# NE-CurrentSense-V2.net
KiCad netlist of a schematic drawn in Altium Designer
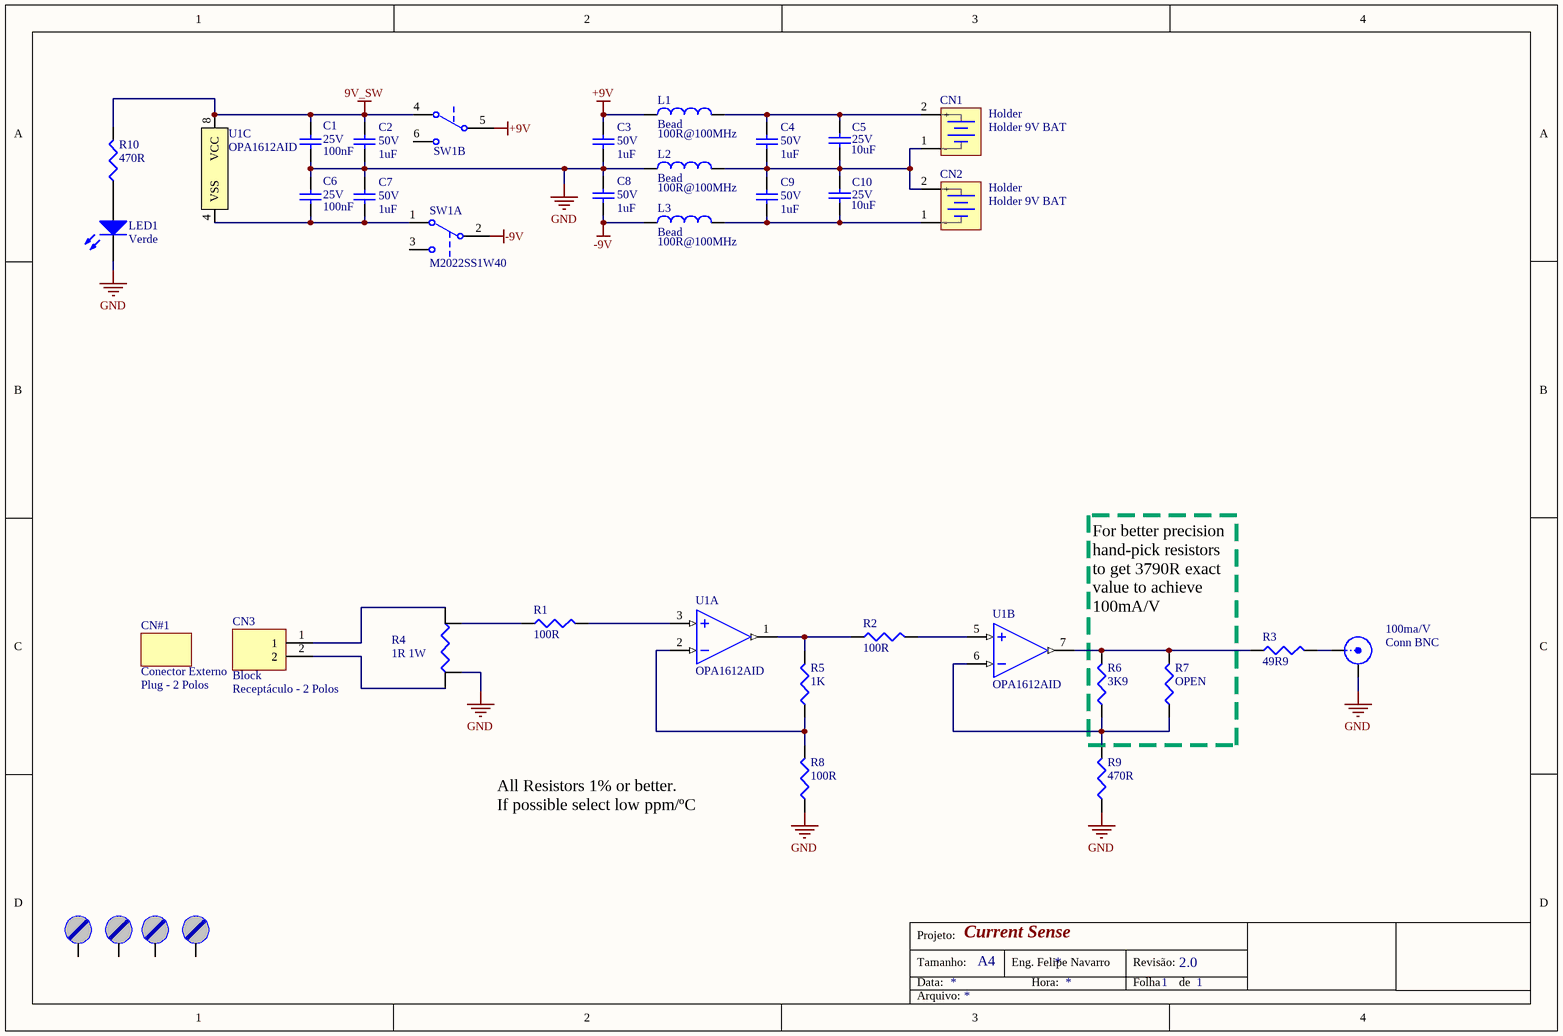
[diagram p0: NE-CurrentSense-V2.SchDoc]

(export (version "E")
  (design (tool "Eeschema 10.0.6"))
  (components
    (comp (ref "100ma/V")
      (value "Conn BNC")
      (footprint "CONN BNC-JACK")
      (description "Conector BNC")
      (libsource (lib "NavarroCON") (part "Conn BNC"))
    )
    (comp (ref "C1")
      (value "100nF")
      (footprint "CC0603")
      (description "Capacitor (Semiconductor SIM Model)")
      (fields (field (name "TENSÃO") "25V") (field (name "Comment") "Capacitor Cerâmico"))
      (libsource (lib "NavarroCAP") (part "Cap 100nF 25V 0603 X7R"))
    )
    (comp (ref "C2")
      (value "1uF")
      (footprint "CC0603")
      (description "Capacitor (Semiconductor SIM Model)")
      (fields (field (name "TENSÃO") "50V") (field (name "Comment") "Capacitor Cerâmico"))
      (libsource (lib "NavarroCAP") (part "Cap 1uF 50V 0603 X5R"))
    )
    (comp (ref "C3")
      (value "1uF")
      (footprint "CC0603")
      (description "Capacitor (Semiconductor SIM Model)")
      (fields (field (name "TENSÃO") "50V") (field (name "Comment") "Capacitor Cerâmico"))
      (libsource (lib "NavarroCAP") (part "Cap 1uF 50V 0603 X5R"))
    )
    (comp (ref "C4")
      (value "1uF")
      (footprint "CC0603")
      (description "Capacitor (Semiconductor SIM Model)")
      (fields (field (name "TENSÃO") "50V") (field (name "Comment") "Capacitor Cerâmico"))
      (libsource (lib "NavarroCAP") (part "Cap 1uF 50V 0603 X5R"))
    )
    (comp (ref "C5")
      (value "10uF")
      (footprint "CC0805")
      (description "Capacitor (Semiconductor SIM Model)")
      (fields (field (name "TENSÃO") "25V") (field (name "Comment") "Capacitor Cerâmico"))
      (libsource (lib "NavarroCAP") (part "Cap 10uF 25V 0805 X5R"))
    )
    (comp (ref "C6")
      (value "100nF")
      (footprint "CC0603")
      (description "Capacitor (Semiconductor SIM Model)")
      (fields (field (name "TENSÃO") "25V") (field (name "Comment") "Capacitor Cerâmico"))
      (libsource (lib "NavarroCAP") (part "Cap 100nF 25V 0603 X7R"))
    )
    (comp (ref "C7")
      (value "1uF")
      (footprint "CC0603")
      (description "Capacitor (Semiconductor SIM Model)")
      (fields (field (name "TENSÃO") "50V") (field (name "Comment") "Capacitor Cerâmico"))
      (libsource (lib "NavarroCAP") (part "Cap 1uF 50V 0603 X5R"))
    )
    (comp (ref "C8")
      (value "1uF")
      (footprint "CC0603")
      (description "Capacitor (Semiconductor SIM Model)")
      (fields (field (name "TENSÃO") "50V") (field (name "Comment") "Capacitor Cerâmico"))
      (libsource (lib "NavarroCAP") (part "Cap 1uF 50V 0603 X5R"))
    )
    (comp (ref "C9")
      (value "1uF")
      (footprint "CC0603")
      (description "Capacitor (Semiconductor SIM Model)")
      (fields (field (name "TENSÃO") "50V") (field (name "Comment") "Capacitor Cerâmico"))
      (libsource (lib "NavarroCAP") (part "Cap 1uF 50V 0603 X5R"))
    )
    (comp (ref "C10")
      (value "10uF")
      (footprint "CC0805")
      (description "Capacitor (Semiconductor SIM Model)")
      (fields (field (name "TENSÃO") "25V") (field (name "Comment") "Capacitor Cerâmico"))
      (libsource (lib "NavarroCAP") (part "Cap 10uF 25V 0805 X5R"))
    )
    (comp (ref "CN#1")
      (value "Conector Externo")
      (footprint "N/A")
      (description "Conector Plug")
      (fields (field (name "ALTIUM_VALUE") "Plug - 2 Polos"))
      (libsource (lib "NavarroCON") (part "Plug Block 2P 3.81mm"))
    )
    (comp (ref "CN1")
      (value "Holder")
      (footprint "BATTHOLDER-9V-BH9V-PC-ND")
      (fields (field (name "ALTIUM_VALUE") "Holder 9V BAT"))
      (libsource (lib "NavarroCON") (part "BattHolder 9V"))
    )
    (comp (ref "CN2")
      (value "Holder")
      (footprint "BATTHOLDER-9V-BH9V-PC-ND")
      (fields (field (name "ALTIUM_VALUE") "Holder 9V BAT"))
      (libsource (lib "NavarroCON") (part "BattHolder 9V"))
    )
    (comp (ref "CN3")
      (value "Block")
      (footprint "CONN BLOCK2 RCPT/H")
      (description "Conector Shrouded Block")
      (fields (field (name "ALTIUM_VALUE") "Receptáculo - 2 Polos"))
      (libsource (lib "NavarroCON") (part "SHRD Block 2P RCPT-H P3.81mm"))
    )
    (comp (ref "HOLE3")
      (value "Furo de Fixação")
      (footprint "Furo_M3")
      (description "Furo para parafuso")
      (libsource (lib "Navarro") (part "Parafuso"))
    )
    (comp (ref "HOLE4")
      (value "Furo de Fixação")
      (footprint "Furo_M3")
      (description "Furo para parafuso")
      (libsource (lib "Navarro") (part "Parafuso"))
    )
    (comp (ref "HOLE5")
      (value "Furo de Fixação")
      (footprint "Furo_M3")
      (description "Furo para parafuso")
      (libsource (lib "Navarro") (part "Parafuso"))
    )
    (comp (ref "L1")
      (value "Bead")
      (footprint "CC0603")
      (fields (field (name "ALTIUM_VALUE") "100R@100MHz"))
      (libsource (lib "NavarroIND") (part "Bd 100R@100MHz 0603 2A"))
    )
    (comp (ref "L2")
      (value "Bead")
      (footprint "CC0603")
      (fields (field (name "ALTIUM_VALUE") "100R@100MHz"))
      (libsource (lib "NavarroIND") (part "Bd 100R@100MHz 0603 2A"))
    )
    (comp (ref "L3")
      (value "Bead")
      (footprint "CC0603")
      (fields (field (name "ALTIUM_VALUE") "100R@100MHz"))
      (libsource (lib "NavarroIND") (part "Bd 100R@100MHz 0603 2A"))
    )
    (comp (ref "LED1")
      (value "Verde")
      (footprint "LED-INDIC")
      (description "Typical RED, GREEN, YELLOW, AMBER GaAs LED")
      (fields (field (name "Comment") "LED"))
      (libsource (lib "Miscellaneous Devices") (part "LED2"))
    )
    (comp (ref "R1")
      (value "100R")
      (footprint "CC0603")
      (description "Resistor")
      (libsource (lib "NavarroRES") (part "Res 100R 5% 0603 1/10W"))
    )
    (comp (ref "R2")
      (value "100R")
      (footprint "CC0603")
      (description "Resistor")
      (libsource (lib "NavarroRES") (part "Res 100R 5% 0603 1/10W"))
    )
    (comp (ref "R3")
      (value "49R9")
      (footprint "CC0603")
      (description "Resistor")
      (libsource (lib "NavarroRES") (part "Res 49R9 1% 0603 1/10W"))
    )
    (comp (ref "R4")
      (value "1R 1W")
      (footprint "CC2516 - Wide Vishay")
      (description "Resistor")
      (libsource (lib "NavarroRES") (part "Res 1R 0.1% CC2516-Wide-4W 1W"))
    )
    (comp (ref "R5")
      (value "1K")
      (footprint "CC0603")
      (description "Resistor")
      (libsource (lib "NavarroRES") (part "Res 1K 0.1% 0603 1/16W"))
    )
    (comp (ref "R6")
      (value "3K9")
      (footprint "CC0603")
      (description "Resistor")
      (libsource (lib "NavarroRES") (part "Res 3K9 1% 0603 1/10W"))
    )
    (comp (ref "R7")
      (value "OPEN")
      (footprint "CC0603")
      (description "Resistor")
      (fields (field (name "Comment") "Resistor Open"))
      (libsource (lib "NavarroRES") (part "Res Open 0603"))
    )
    (comp (ref "R8")
      (value "100R")
      (footprint "CC0603")
      (description "Resistor")
      (libsource (lib "NavarroRES") (part "Res 100R 5% 0603 1/10W"))
    )
    (comp (ref "R9")
      (value "470R")
      (footprint "CC0603")
      (description "Resistor")
      (libsource (lib "NavarroRES") (part "Res 470R 5% 0603 1/10W"))
    )
    (comp (ref "R10")
      (value "470R")
      (footprint "CC0603")
      (description "Resistor")
      (libsource (lib "NavarroRES") (part "Res 470R 5% 0603 1/10W"))
    )
    (comp (ref "SW1")
      (value "M2022SS1W40")
      (footprint "SWITCH TOGGLE DPDT 6A 125V")
      (description "Double-Pole, Double-Throw Switch")
      (libsource (lib "") (part "SW-DPDT_1"))
    )
    (comp (ref "U1")
      (value "OPA1612AID")
      (footprint "SOIC-8N")
      (description "OPAx197 36-V, Precision, Rail-to-Rail Input/Output, Low Offset Voltage, Operational Amplifiers")
      (libsource (lib "Navarro") (part "OPA2197"))
    )
  )
  (nets
    (net (code "1") (name "+9V") (class "Default")
      (node (ref "C3") (pin "2") (pinfunction "2_2") (pintype "passive"))
      (node (ref "L1") (pin "1") (pinfunction "1_1") (pintype "passive"))
      (node (ref "SW1") (pin "5") (pinfunction "C2_5") (pintype "passive"))
    )
    (net (code "2") (name "-9V") (class "Default")
      (node (ref "C8") (pin "1") (pinfunction "1_1") (pintype "passive"))
      (node (ref "L3") (pin "1") (pinfunction "1_1") (pintype "passive"))
      (node (ref "SW1") (pin "2") (pinfunction "C1_2") (pintype "passive"))
    )
    (net (code "3") (name "9V_SW") (class "Default")
      (node (ref "C1") (pin "2") (pinfunction "2_2") (pintype "passive"))
      (node (ref "C2") (pin "2") (pinfunction "2_2") (pintype "passive"))
      (node (ref "R10") (pin "2") (pinfunction "2_2") (pintype "passive"))
      (node (ref "SW1") (pin "4") (pinfunction "NC2_4") (pintype "passive"))
      (node (ref "U1") (pin "8") (pinfunction "VCC_8") (pintype "power_in"))
    )
    (net (code "4") (name "GND") (class "Default")
      (node (ref "100ma/V") (pin "2") (pinfunction "Y_2") (pintype "passive"))
      (node (ref "C1") (pin "1") (pinfunction "1_1") (pintype "passive"))
      (node (ref "C2") (pin "1") (pinfunction "1_1") (pintype "passive"))
      (node (ref "C3") (pin "1") (pinfunction "1_1") (pintype "passive"))
      (node (ref "C6") (pin "2") (pinfunction "2_2") (pintype "passive"))
      (node (ref "C7") (pin "2") (pinfunction "2_2") (pintype "passive"))
      (node (ref "C8") (pin "2") (pinfunction "2_2") (pintype "passive"))
      (node (ref "L2") (pin "1") (pinfunction "1_1") (pintype "passive"))
      (node (ref "LED1") (pin "2") (pinfunction "K_2") (pintype "passive"))
      (node (ref "R4") (pin "2") (pinfunction "2_2") (pintype "passive"))
      (node (ref "R8") (pin "1") (pinfunction "1_1") (pintype "passive"))
      (node (ref "R9") (pin "1") (pinfunction "1_1") (pintype "passive"))
    )
    (net (code "5") (name "Net-(100ma/V-X)") (class "Default")
      (node (ref "100ma/V") (pin "1") (pinfunction "X_1") (pintype "passive"))
      (node (ref "R3") (pin "2") (pinfunction "2_2") (pintype "passive"))
    )
    (net (code "6") (name "Net-(CN1-+)") (class "Default")
      (node (ref "C4") (pin "2") (pinfunction "2_2") (pintype "passive"))
      (node (ref "C5") (pin "2") (pinfunction "2_2") (pintype "passive"))
      (node (ref "CN1") (pin "2") (pinfunction "+_2") (pintype "power_in"))
      (node (ref "L1") (pin "2") (pinfunction "2_2") (pintype "passive"))
    )
    (net (code "7") (name "Net-(CN1--)") (class "Default")
      (node (ref "C10") (pin "2") (pinfunction "2_2") (pintype "passive"))
      (node (ref "C4") (pin "1") (pinfunction "1_1") (pintype "passive"))
      (node (ref "C5") (pin "1") (pinfunction "1_1") (pintype "passive"))
      (node (ref "C9") (pin "2") (pinfunction "2_2") (pintype "passive"))
      (node (ref "CN1") (pin "1") (pinfunction "-_1") (pintype "power_in"))
      (node (ref "CN2") (pin "2") (pinfunction "+_2") (pintype "power_in"))
      (node (ref "L2") (pin "2") (pinfunction "2_2") (pintype "passive"))
    )
    (net (code "8") (name "Net-(CN2--)") (class "Default")
      (node (ref "C10") (pin "1") (pinfunction "1_1") (pintype "passive"))
      (node (ref "C9") (pin "1") (pinfunction "1_1") (pintype "passive"))
      (node (ref "CN2") (pin "1") (pinfunction "-_1") (pintype "power_in"))
      (node (ref "L3") (pin "2") (pinfunction "2_2") (pintype "passive"))
    )
    (net (code "9") (name "Net-(CN3-Pad1)") (class "Default")
      (node (ref "CN3") (pin "1") (pinfunction "1_1") (pintype "passive"))
      (node (ref "R4") (pin "3") (pinfunction "3_3") (pintype "passive"))
    )
    (net (code "10") (name "Net-(CN3-Pad2)") (class "Default")
      (node (ref "CN3") (pin "2") (pinfunction "2_2") (pintype "passive"))
      (node (ref "R4") (pin "1") (pinfunction "1_1") (pintype "passive"))
    )
    (net (code "11") (name "Net-(LED1-A)") (class "Default")
      (node (ref "LED1") (pin "1") (pinfunction "A_1") (pintype "passive"))
      (node (ref "R10") (pin "1") (pinfunction "1_1") (pintype "passive"))
    )
    (net (code "12") (name "Net-(R1-Pad1)") (class "Default")
      (node (ref "R1") (pin "1") (pinfunction "1_1") (pintype "passive"))
      (node (ref "R4") (pin "4") (pinfunction "4_4") (pintype "passive"))
    )
    (net (code "13") (name "Net-(SW1A-NC1)") (class "Default")
      (node (ref "C6") (pin "1") (pinfunction "1_1") (pintype "passive"))
      (node (ref "C7") (pin "1") (pinfunction "1_1") (pintype "passive"))
      (node (ref "SW1") (pin "1") (pinfunction "NC1_1") (pintype "passive"))
      (node (ref "U1") (pin "4") (pinfunction "VSS_4") (pintype "power_in"))
    )
    (net (code "14") (name "Net-(U1A-INA+)") (class "Default")
      (node (ref "R1") (pin "2") (pinfunction "2_2") (pintype "passive"))
      (node (ref "U1") (pin "3") (pinfunction "INA+_3") (pintype "input"))
    )
    (net (code "15") (name "Net-(U1A-INA-)") (class "Default")
      (node (ref "R5") (pin "1") (pinfunction "1_1") (pintype "passive"))
      (node (ref "R8") (pin "2") (pinfunction "2_2") (pintype "passive"))
      (node (ref "U1") (pin "2") (pinfunction "INA-_2") (pintype "input"))
    )
    (net (code "16") (name "Net-(U1A-OUTA)") (class "Default")
      (node (ref "R2") (pin "1") (pinfunction "1_1") (pintype "passive"))
      (node (ref "R5") (pin "2") (pinfunction "2_2") (pintype "passive"))
      (node (ref "U1") (pin "1") (pinfunction "OUTA_1") (pintype "output"))
    )
    (net (code "17") (name "Net-(U1B-INB+)") (class "Default")
      (node (ref "R2") (pin "2") (pinfunction "2_2") (pintype "passive"))
      (node (ref "U1") (pin "5") (pinfunction "INB+_5") (pintype "input"))
    )
    (net (code "18") (name "Net-(U1B-INB-)") (class "Default")
      (node (ref "R6") (pin "1") (pinfunction "1_1") (pintype "passive"))
      (node (ref "R7") (pin "1") (pinfunction "1_1") (pintype "passive"))
      (node (ref "R9") (pin "2") (pinfunction "2_2") (pintype "passive"))
      (node (ref "U1") (pin "6") (pinfunction "INB-_6") (pintype "input"))
    )
    (net (code "19") (name "Net-(U1B-OUTB)") (class "Default")
      (node (ref "R3") (pin "1") (pinfunction "1_1") (pintype "passive"))
      (node (ref "R6") (pin "2") (pinfunction "2_2") (pintype "passive"))
      (node (ref "R7") (pin "2") (pinfunction "2_2") (pintype "passive"))
      (node (ref "U1") (pin "7") (pinfunction "OUTB_7") (pintype "output"))
    )
    (net (code "20") (name "unconnected-(HOLE3-PadX)") (class "Default")
      (node (ref "HOLE3") (pin "X") (pinfunction "X_X") (pintype "passive"))
    )
    (net (code "21") (name "unconnected-(HOLE4-PadX)") (class "Default")
      (node (ref "HOLE4") (pin "X") (pinfunction "X_X") (pintype "passive"))
    )
    (net (code "22") (name "unconnected-(HOLE4-PadX)_1") (class "Default")
      (node (ref "HOLE4") (pin "X") (pinfunction "X_X") (pintype "passive"))
    )
    (net (code "23") (name "unconnected-(HOLE5-PadX)") (class "Default")
      (node (ref "HOLE5") (pin "X") (pinfunction "X_X") (pintype "passive"))
    )
    (net (code "24") (name "unconnected-(SW1A-NO1-Pad3)") (class "Default")
      (node (ref "SW1") (pin "3") (pinfunction "NO1_3") (pintype "passive"))
    )
    (net (code "25") (name "unconnected-(SW1B-NO2-Pad6)") (class "Default")
      (node (ref "SW1") (pin "6") (pinfunction "NO2_6") (pintype "passive"))
    )
  )
)
